# eth_100base-tx_magnetics.net
KiCad netlist of a schematic drawn in Altium Designer
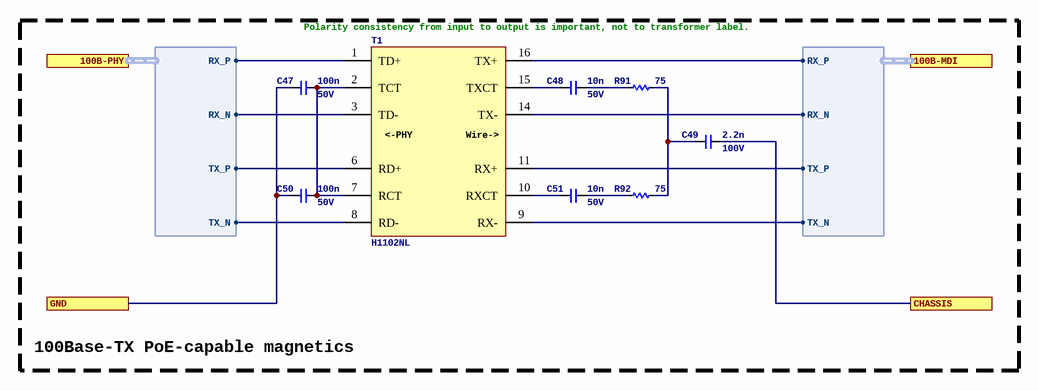
[diagram p0: eth_100base-tx_magnetics.SchDoc]

(export (version "E")
  (design (tool "Eeschema 10.0.6"))
  (components
    (comp (ref "C47")
      (value "CL05B104KB54PNC")
      (footprint "C0402")
      (fields
        (field (name "CAPACITANCE") "100n")
        (field (name "MANUFACTURER") "Samsung Electro-Mechanics")
        (field (name "VOLTAGE RATING") "50V")
      )
      (libsource (lib "database") (part "__template_cap"))
    )
    (comp (ref "C48")
      (value "CL05B103KB5NNNC")
      (footprint "C0402")
      (fields
        (field (name "CAPACITANCE") "10n")
        (field (name "MANUFACTURER") "Samsung Electro-Mechanics")
        (field (name "VOLTAGE RATING") "50V")
      )
      (libsource (lib "database") (part "__template_cap"))
    )
    (comp (ref "C49")
      (value "CC0402KRX7R0BB222")
      (footprint "C0402")
      (fields
        (field (name "CAPACITANCE") "2.2n")
        (field (name "MANUFACTURER") "YAGEO")
        (field (name "VOLTAGE RATING") "100V")
      )
      (libsource (lib "database") (part "__template_cap"))
    )
    (comp (ref "C50")
      (value "CL05B104KB54PNC")
      (footprint "C0402")
      (fields
        (field (name "CAPACITANCE") "100n")
        (field (name "MANUFACTURER") "Samsung Electro-Mechanics")
        (field (name "VOLTAGE RATING") "50V")
      )
      (libsource (lib "database") (part "__template_cap"))
    )
    (comp (ref "C51")
      (value "CL05B103KB5NNNC")
      (footprint "C0402")
      (fields
        (field (name "CAPACITANCE") "10n")
        (field (name "MANUFACTURER") "Samsung Electro-Mechanics")
        (field (name "VOLTAGE RATING") "50V")
      )
      (libsource (lib "database") (part "__template_cap"))
    )
    (comp (ref "R91")
      (value "75")
      (footprint "R0402")
      (fields
        (field (name "TOLERANCE") "1%")
        (field (name "MANUFACTURER PART NUMBER") "0402WGF750JTCE")
        (field (name "MANUFACTURER") "UNI-ROYAL(Uniroyal Elec)")
      )
      (libsource (lib "database") (part "__template_resistor"))
    )
    (comp (ref "R92")
      (value "75")
      (footprint "R0402")
      (fields
        (field (name "TOLERANCE") "1%")
        (field (name "MANUFACTURER PART NUMBER") "0402WGF750JTCE")
        (field (name "MANUFACTURER") "UNI-ROYAL(Uniroyal Elec)")
      )
      (libsource (lib "database") (part "__template_resistor"))
    )
    (comp (ref "T1")
      (value "H1102NL")
      (footprint "EPCOS_LAN_MODULE")
      (description "MODULE XFRMR SGL ETHR LAN 16SOIC")
      (fields
        (field (name "MANUFACTURER") "Pulse Electronics Corporation")
        (field (name "MANUFACTURER PART NUMBER") "H1102NL")
      )
      (libsource (lib "SSCP") (part "ETH_H1102NL"))
    )
  )
  (nets
    (net (code "2") (name "/CHASSIS") (class "Default") (node (ref "C49") (pin "2") (pintype "passive")))
    (net (code "3") (name "/GND") (class "Default")
      (node (ref "C47") (pin "2") (pintype "passive"))
      (node (ref "C50") (pin "2") (pintype "passive"))
    )
    (net (code "5") (name "Net-(C48-Pad2)") (class "Default")
      (node (ref "C48") (pin "2") (pintype "passive"))
      (node (ref "R91") (pin "2") (pintype "passive"))
    )
    (net (code "6") (name "Net-(C49-Pad1)") (class "Default")
      (node (ref "C49") (pin "1") (pintype "passive"))
      (node (ref "R91") (pin "1") (pintype "passive"))
      (node (ref "R92") (pin "1") (pintype "passive"))
    )
    (net (code "7") (name "Net-(C51-Pad2)") (class "Default")
      (node (ref "C51") (pin "2") (pintype "passive"))
      (node (ref "R92") (pin "2") (pintype "passive"))
    )
    (net (code "8") (name "Net-(T1-RCT)") (class "Default")
      (node (ref "C47") (pin "1") (pintype "passive"))
      (node (ref "C50") (pin "1") (pintype "passive"))
      (node (ref "T1") (pin "2") (pinfunction "TCT_2") (pintype "passive"))
      (node (ref "T1") (pin "7") (pinfunction "RCT_7") (pintype "passive"))
    )
    (net (code "9") (name "Net-(T1-RXCT)") (class "Default")
      (node (ref "C51") (pin "1") (pintype "passive"))
      (node (ref "T1") (pin "10") (pinfunction "RXCT_10") (pintype "passive"))
    )
    (net (code "10") (name "Net-(T1-TXCT)") (class "Default")
      (node (ref "C48") (pin "1") (pintype "passive"))
      (node (ref "T1") (pin "15") (pinfunction "TXCT_15") (pintype "passive"))
    )
    (net (code "11") (name "unconnected-(T1-RD+-Pad6)") (class "Default")
      (node (ref "T1") (pin "6") (pinfunction "RD+_6") (pintype "passive"))
    )
    (net (code "12") (name "unconnected-(T1-RD--Pad8)") (class "Default")
      (node (ref "T1") (pin "8") (pinfunction "RD-_8") (pintype "passive"))
    )
    (net (code "13") (name "unconnected-(T1-RX+-Pad11)") (class "Default")
      (node (ref "T1") (pin "11") (pinfunction "RX+_11") (pintype "passive"))
    )
    (net (code "14") (name "unconnected-(T1-RX--Pad9)") (class "Default")
      (node (ref "T1") (pin "9") (pinfunction "RX-_9") (pintype "passive"))
    )
    (net (code "15") (name "unconnected-(T1-TD+-Pad1)") (class "Default")
      (node (ref "T1") (pin "1") (pinfunction "TD+_1") (pintype "passive"))
    )
    (net (code "16") (name "unconnected-(T1-TD--Pad3)") (class "Default")
      (node (ref "T1") (pin "3") (pinfunction "TD-_3") (pintype "passive"))
    )
    (net (code "17") (name "unconnected-(T1-TX+-Pad16)") (class "Default")
      (node (ref "T1") (pin "16") (pinfunction "TX+_16") (pintype "passive"))
    )
    (net (code "18") (name "unconnected-(T1-TX--Pad14)") (class "Default")
      (node (ref "T1") (pin "14") (pinfunction "TX-_14") (pintype "passive"))
    )
  )
)
